# sensorfix.net
KiCad netlist of a schematic drawn in EAGLE
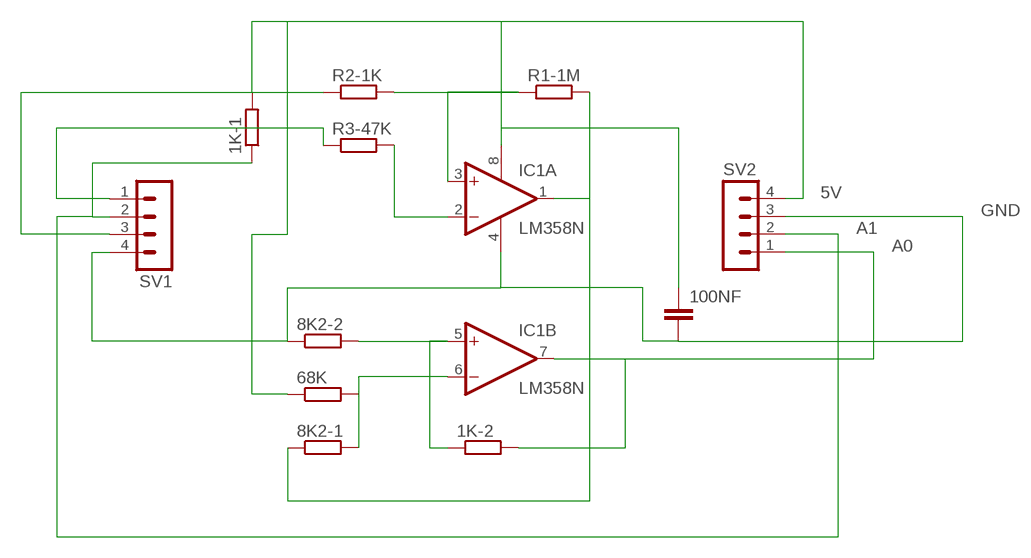
[diagram p0: schematic, sheet 1]

(export (version "E")
  (design (tool "Eeschema 10.0.6"))
  (components
    (comp (ref "1K-1")
      (value "R-EU_0309/12")
      (footprint "eagle-import:0309_12")
      (libsource (lib "eagle-import") (part "R-EU_0309/12"))
    )
    (comp (ref "1K-2")
      (value "R-EU_0309/12")
      (footprint "eagle-import:0309_12")
      (libsource (lib "eagle-import") (part "R-EU_0309/12"))
    )
    (comp (ref "8K2-1")
      (value "R-EU_0309/12")
      (footprint "eagle-import:0309_12")
      (libsource (lib "eagle-import") (part "R-EU_0309/12"))
    )
    (comp (ref "8K2-2")
      (value "R-EU_0309/12")
      (footprint "eagle-import:0309_12")
      (libsource (lib "eagle-import") (part "R-EU_0309/12"))
    )
    (comp (ref "68K")
      (value "R-EU_0309/12")
      (footprint "eagle-import:0309_12")
      (libsource (lib "eagle-import") (part "R-EU_0309/12"))
    )
    (comp (ref "100NF")
      (value "C2.5/6")
      (footprint "eagle-import:C2.5-6")
      (libsource (lib "eagle-import") (part "C2.5/6"))
    )
    (comp (ref "IC1")
      (value "LM358N")
      (footprint "eagle-import:DIL08")
      (libsource (lib "eagle-import") (part "LM358N"))
    )
    (comp (ref "R1-1M")
      (value "R-EU_0309/12")
      (footprint "eagle-import:0309_12")
      (libsource (lib "eagle-import") (part "R-EU_0309/12"))
    )
    (comp (ref "R2-1K")
      (value "R-EU_0309/12")
      (footprint "eagle-import:0309_12")
      (libsource (lib "eagle-import") (part "R-EU_0309/12"))
    )
    (comp (ref "R3-47K")
      (value "R-EU_0309/12")
      (footprint "eagle-import:0309_12")
      (libsource (lib "eagle-import") (part "R-EU_0309/12"))
    )
    (comp (ref "SV1")
      (value "MA04-1")
      (footprint "eagle-import:MA04-1")
      (libsource (lib "eagle-import") (part "MA04-1"))
    )
    (comp (ref "SV2")
      (value "MA04-1")
      (footprint "eagle-import:MA04-1")
      (libsource (lib "eagle-import") (part "MA04-1"))
    )
  )
  (nets
    (net (code "1") (name "/5V") (class "Default")
      (node (ref "100NF") (pin "1") (pinfunction "1_1") (pintype "passive"))
      (node (ref "1K-1") (pin "2") (pinfunction "2_2") (pintype "passive"))
      (node (ref "68K") (pin "1") (pinfunction "1_1") (pintype "passive"))
      (node (ref "IC1") (pin "8") (pinfunction "V+_8") (pintype "power_in"))
      (node (ref "SV2") (pin "4") (pinfunction "4_4") (pintype "passive"))
    )
    (net (code "2") (name "/A0") (class "Default")
      (node (ref "1K-2") (pin "2") (pinfunction "2_2") (pintype "passive"))
      (node (ref "IC1") (pin "7") (pinfunction "OUT_7") (pintype "output"))
      (node (ref "SV2") (pin "1") (pinfunction "1_1") (pintype "passive"))
    )
    (net (code "3") (name "/A1") (class "Default")
      (node (ref "1K-1") (pin "1") (pinfunction "1_1") (pintype "passive"))
      (node (ref "SV1") (pin "2") (pinfunction "2_2") (pintype "passive"))
      (node (ref "SV2") (pin "2") (pinfunction "2_2") (pintype "passive"))
    )
    (net (code "4") (name "/GND") (class "Default")
      (node (ref "100NF") (pin "2") (pinfunction "2_2") (pintype "passive"))
      (node (ref "8K2-2") (pin "1") (pinfunction "1_1") (pintype "passive"))
      (node (ref "IC1") (pin "4") (pinfunction "V-_4") (pintype "power_in"))
      (node (ref "SV1") (pin "4") (pinfunction "4_4") (pintype "passive"))
      (node (ref "SV2") (pin "3") (pinfunction "3_3") (pintype "passive"))
    )
    (net (code "5") (name "Net-(IC1A-+IN)") (class "Default")
      (node (ref "IC1") (pin "3") (pinfunction "+IN_3") (pintype "input"))
      (node (ref "R1-1M") (pin "1") (pinfunction "1_1") (pintype "passive"))
      (node (ref "R2-1K") (pin "2") (pinfunction "2_2") (pintype "passive"))
    )
    (net (code "6") (name "Net-(IC1A--IN)") (class "Default")
      (node (ref "IC1") (pin "2") (pinfunction "-IN_2") (pintype "input"))
      (node (ref "R3-47K") (pin "2") (pinfunction "2_2") (pintype "passive"))
    )
    (net (code "7") (name "Net-(IC1A-OUT)") (class "Default")
      (node (ref "8K2-1") (pin "1") (pinfunction "1_1") (pintype "passive"))
      (node (ref "IC1") (pin "1") (pinfunction "OUT_1") (pintype "output"))
      (node (ref "R1-1M") (pin "2") (pinfunction "2_2") (pintype "passive"))
    )
    (net (code "8") (name "Net-(IC1B-+IN)") (class "Default")
      (node (ref "1K-2") (pin "1") (pinfunction "1_1") (pintype "passive"))
      (node (ref "8K2-2") (pin "2") (pinfunction "2_2") (pintype "passive"))
      (node (ref "IC1") (pin "5") (pinfunction "+IN_5") (pintype "input"))
    )
    (net (code "9") (name "Net-(IC1B--IN)") (class "Default")
      (node (ref "68K") (pin "2") (pinfunction "2_2") (pintype "passive"))
      (node (ref "8K2-1") (pin "2") (pinfunction "2_2") (pintype "passive"))
      (node (ref "IC1") (pin "6") (pinfunction "-IN_6") (pintype "input"))
    )
    (net (code "10") (name "Net-(R2-1K-Pad1)") (class "Default")
      (node (ref "R2-1K") (pin "1") (pinfunction "1_1") (pintype "passive"))
      (node (ref "SV1") (pin "3") (pinfunction "3_3") (pintype "passive"))
    )
    (net (code "11") (name "Net-(R3-47K-Pad1)") (class "Default")
      (node (ref "R3-47K") (pin "1") (pinfunction "1_1") (pintype "passive"))
      (node (ref "SV1") (pin "1") (pinfunction "1_1") (pintype "passive"))
    )
  )
)
